# Controlador_de_velocidad_v2.net
KiCad netlist of a schematic drawn in Altium Designer
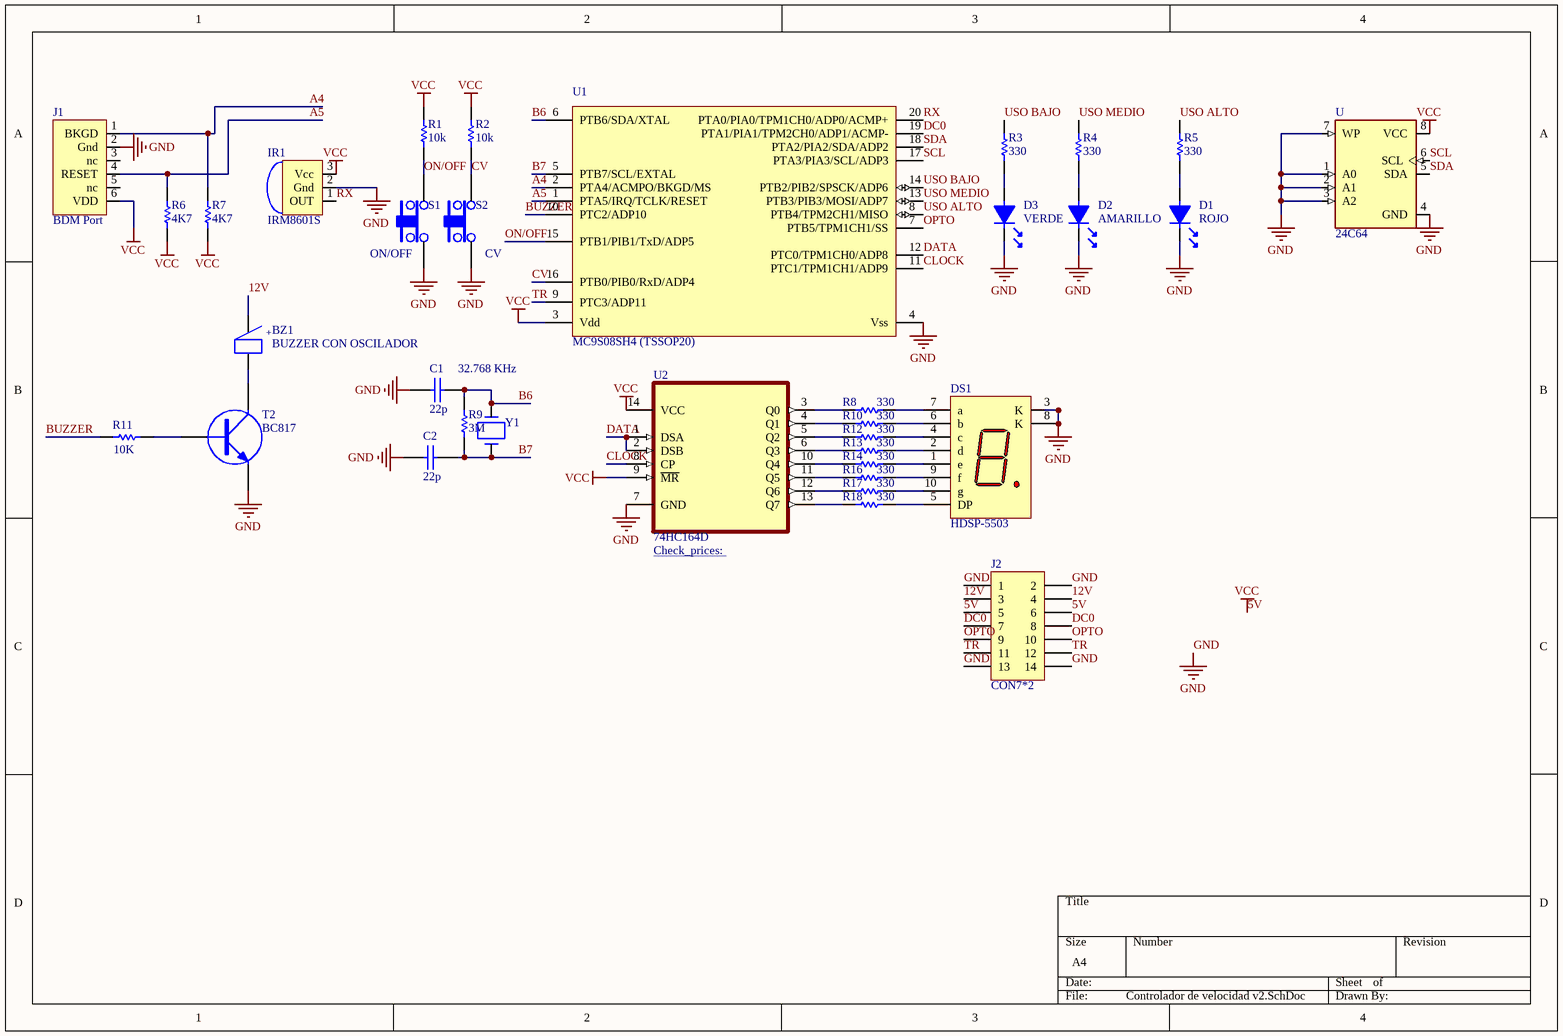
[diagram p0: Controlador de velocidad v2.SchDoc]

(export (version "E")
  (design (tool "Eeschema 10.0.6"))
  (components
    (comp (ref "BZ1")
      (value "BUZZER CON OSCILADOR")
      (footprint "BUZZER 12MM")
      (libsource (lib "LIBEBAL") (part "BUZZER"))
    )
    (comp (ref "C1") (value "22p") (footprint "0805") (libsource (lib "LIBPIOIX") (part "CAP")))
    (comp (ref "C2") (value "22p") (footprint "0805") (libsource (lib "LIBPIOIX") (part "CAP")))
    (comp (ref "D1") (value "ROJO") (footprint "LED5") (libsource (lib "LIBPIOIX") (part "LED")))
    (comp (ref "D2") (value "AMARILLO") (footprint "LED5") (libsource (lib "LIBPIOIX") (part "LED")))
    (comp (ref "D3") (value "VERDE") (footprint "LED5") (libsource (lib "LIBPIOIX") (part "LED")))
    (comp (ref "DS1")
      (value "HDSP-5503")
      (footprint "H-10")
      (description "14.22 mm Gray Surface HER 7-Segment Display: CC, RH DP")
      (fields (field (name "PUBLISHER") "Altium Limited"))
      (libsource (lib "Agilent LED Display 7-Segment, 1-Digit") (part "HDSP-5503"))
    )
    (comp (ref "IR1")
      (value "IRM8601S")
      (footprint "IRM8601S")
      (description "Sensor IR")
      (libsource (lib "*") (part "IRM8601S"))
    )
    (comp (ref "J1") (value "BDM Port") (footprint "JBDM") (libsource (lib "*") (part "JBDM")))
    (comp (ref "J2") (value "CON7*2") (footprint "SIP7*2") (libsource (lib "LIBEBAL") (part "CON7*2")))
    (comp (ref "R1") (value "10k") (footprint "0805") (libsource (lib "LIBPIOIX") (part "RES")))
    (comp (ref "R2") (value "10k") (footprint "0805") (libsource (lib "LIBPIOIX") (part "RES")))
    (comp (ref "R3") (value "330") (footprint "0805") (libsource (lib "LIBPIOIX") (part "RES")))
    (comp (ref "R4") (value "330") (footprint "0805") (libsource (lib "LIBPIOIX") (part "RES")))
    (comp (ref "R5") (value "330") (footprint "0805") (libsource (lib "LIBPIOIX") (part "RES")))
    (comp (ref "R6") (value "4K7") (footprint "0805") (libsource (lib "LIBPIOIX") (part "RES")))
    (comp (ref "R7") (value "4K7") (footprint "0805") (libsource (lib "LIBPIOIX") (part "RES")))
    (comp (ref "R8") (value "330") (footprint "0805") (libsource (lib "LIB PIO IX") (part "RES")))
    (comp (ref "R9") (value "3M") (footprint "0805") (libsource (lib "LIB PIO IX") (part "RES")))
    (comp (ref "R10") (value "330") (footprint "0805") (libsource (lib "LIB PIO IX") (part "RES")))
    (comp (ref "R11") (value "10K") (footprint "0805") (libsource (lib "LIBPIOIX") (part "RES")))
    (comp (ref "R12") (value "330") (footprint "0805") (libsource (lib "LIB PIO IX") (part "RES")))
    (comp (ref "R13") (value "330") (footprint "0805") (libsource (lib "LIB PIO IX") (part "RES")))
    (comp (ref "R14") (value "330") (footprint "0805") (libsource (lib "LIB PIO IX") (part "RES")))
    (comp (ref "R16") (value "330") (footprint "0805") (libsource (lib "LIB PIO IX") (part "RES")))
    (comp (ref "R17") (value "330") (footprint "0805") (libsource (lib "LIB PIO IX") (part "RES")))
    (comp (ref "R18") (value "330") (footprint "0805") (libsource (lib "LIB PIO IX") (part "RES")))
    (comp (ref "S1")
      (value "ON/OFF")
      (footprint "TACTSWITCH")
      (libsource (lib "LIBPIOIX") (part "TACT SWITCH"))
    )
    (comp (ref "S2") (value "CV") (footprint "TACTSWITCH") (libsource (lib "LIBPIOIX") (part "TACT SWITCH")))
    (comp (ref "T2") (value "BC817") (footprint "SOT23") (libsource (lib "LIBPIOIX") (part "TRANSISTOR NPN")))
    (comp (ref "U")
      (value "24C64")
      (footprint "SOIC127P600X175-8N")
      (description "EEPROM Memory IC 256Kb _32K x 8_ I²C 1MHz 550ns 8-SOIC")
      (fields
        (field (name "MP") "AT24C256C-SSHL-T")
        (field (name "DIGI-KEY_PART_NUMBER") "AT24C256C-SSHL-TCT-ND")
      )
      (libsource (lib "AT24C256C-SSHL-T") (part "AT24C256C-SSHL-T"))
    )
    (comp (ref "U1")
      (value "MC9S08SH4 (TSSOP20)")
      (footprint "TSSOP20")
      (libsource (lib "*") (part "MC9S08SH8_20"))
    )
    (comp (ref "U2")
      (value "74HC164D")
      (footprint "SOIC127P600X175-14N")
      (description "Shift Shift Register 1 Element 8 Bit 14-SO")
      (fields (field (name "MF") "Nexperia USA") (field (name "MP") "74HC164D,653"))
      (libsource (lib "74HC164D_653") (part "74HC164D,653"))
    )
    (comp (ref "Y1") (value "32.768 KHz") (footprint "X32768") (libsource (lib "*") (part "CRYSTAL")))
  )
  (nets
    (net (code "1") (name "/12V") (class "Default")
      (node (ref "BZ1") (pin "1") (pinfunction "1_1") (pintype "passive"))
      (node (ref "J2") (pin "3") (pinfunction "3_3") (pintype "passive"))
      (node (ref "J2") (pin "4") (pinfunction "4_4") (pintype "passive"))
    )
    (net (code "2") (name "/A4") (class "Default")
      (node (ref "J1") (pin "1") (pinfunction "BKGD_1") (pintype "passive"))
      (node (ref "R7") (pin "2") (pinfunction "2_2") (pintype "passive"))
      (node (ref "U1") (pin "2") (pinfunction "PTA4/ACMPO/BKGD/MS_2") (pintype "passive"))
    )
    (net (code "3") (name "/A5") (class "Default")
      (node (ref "J1") (pin "4") (pinfunction "RESET_4") (pintype "passive"))
      (node (ref "R6") (pin "2") (pinfunction "2_2") (pintype "passive"))
      (node (ref "U1") (pin "1") (pinfunction "PTA5/IRQ/TCLK/RESET_1") (pintype "passive"))
    )
    (net (code "4") (name "/B6") (class "Default")
      (node (ref "C1") (pin "1") (pinfunction "1_1") (pintype "passive"))
      (node (ref "R9") (pin "2") (pinfunction "2_2") (pintype "passive"))
      (node (ref "U1") (pin "6") (pinfunction "PTB6/SDA/XTAL_6") (pintype "passive"))
      (node (ref "Y1") (pin "2") (pinfunction "2_2") (pintype "passive"))
    )
    (net (code "5") (name "/B7") (class "Default")
      (node (ref "C2") (pin "1") (pinfunction "1_1") (pintype "passive"))
      (node (ref "R9") (pin "1") (pinfunction "1_1") (pintype "passive"))
      (node (ref "U1") (pin "5") (pinfunction "PTB7/SCL/EXTAL_5") (pintype "passive"))
      (node (ref "Y1") (pin "1") (pinfunction "1_1") (pintype "passive"))
    )
    (net (code "6") (name "/BUZZER") (class "Default")
      (node (ref "R11") (pin "1") (pinfunction "1_1") (pintype "passive"))
      (node (ref "U1") (pin "10") (pinfunction "PTC2/ADP10_10") (pintype "passive"))
    )
    (net (code "7") (name "/CLOCK") (class "Default")
      (node (ref "U1") (pin "11") (pinfunction "PTC1/TPM1CH1/ADP9_11") (pintype "passive"))
      (node (ref "U2") (pin "8") (pinfunction "CP_8") (pintype "input"))
    )
    (net (code "8") (name "/CV") (class "Default")
      (node (ref "R2") (pin "1") (pinfunction "1_1") (pintype "passive"))
      (node (ref "S2") (pin "2") (pinfunction "2_2") (pintype "passive"))
      (node (ref "U1") (pin "16") (pinfunction "PTB0/PIB0/RxD/ADP4_16") (pintype "passive"))
    )
    (net (code "9") (name "/DATA") (class "Default")
      (node (ref "U1") (pin "12") (pinfunction "PTC0/TPM1CH0/ADP8_12") (pintype "passive"))
      (node (ref "U2") (pin "1") (pinfunction "DSA_1") (pintype "input"))
      (node (ref "U2") (pin "2") (pinfunction "DSB_2") (pintype "input"))
    )
    (net (code "10") (name "/DC0") (class "Default")
      (node (ref "J2") (pin "7") (pinfunction "7_7") (pintype "passive"))
      (node (ref "J2") (pin "8") (pinfunction "8_8") (pintype "passive"))
      (node (ref "U1") (pin "19") (pinfunction "PTA1/PIA1/TPM2CH0/ADP1/ACMP-_19") (pintype "passive"))
    )
    (net (code "11") (name "/ON{slash}OFF") (class "Default")
      (node (ref "R1") (pin "1") (pinfunction "1_1") (pintype "passive"))
      (node (ref "S1") (pin "2") (pinfunction "2_2") (pintype "passive"))
      (node (ref "U1") (pin "15") (pinfunction "PTB1/PIB1/TxD/ADP5_15") (pintype "passive"))
    )
    (net (code "12") (name "/OPTO") (class "Default")
      (node (ref "J2") (pin "10") (pinfunction "10_10") (pintype "passive"))
      (node (ref "J2") (pin "9") (pinfunction "9_9") (pintype "passive"))
      (node (ref "U1") (pin "7") (pinfunction "PTB5/TPM1CH1/SS_7") (pintype "passive"))
    )
    (net (code "13") (name "/RX") (class "Default")
      (node (ref "IR1") (pin "1") (pinfunction "OUT_1") (pintype "passive"))
      (node (ref "U1") (pin "20") (pinfunction "PTA0/PIA0/TPM1CH0/ADP0/ACMP+_20") (pintype "passive"))
    )
    (net (code "14") (name "/SCL") (class "Default")
      (node (ref "U") (pin "6") (pinfunction "SCL_6") (pintype "input"))
      (node (ref "U1") (pin "17") (pinfunction "PTA3/PIA3/SCL/ADP3_17") (pintype "passive"))
    )
    (net (code "15") (name "/SDA") (class "Default")
      (node (ref "U") (pin "5") (pinfunction "SDA_5") (pintype "bidirectional"))
      (node (ref "U1") (pin "18") (pinfunction "PTA2/PIA2/SDA/ADP2_18") (pintype "passive"))
    )
    (net (code "16") (name "/TR") (class "Default")
      (node (ref "J2") (pin "11") (pinfunction "11_11") (pintype "passive"))
      (node (ref "J2") (pin "12") (pinfunction "12_12") (pintype "passive"))
      (node (ref "U1") (pin "9") (pinfunction "PTC3/ADP11_9") (pintype "passive"))
    )
    (net (code "17") (name "/USO ALTO") (class "Default")
      (node (ref "R5") (pin "2") (pinfunction "2_2") (pintype "passive"))
      (node (ref "U1") (pin "8") (pinfunction "PTB4/TPM2CH1/MISO_8") (pintype "bidirectional"))
    )
    (net (code "18") (name "/USO BAJO") (class "Default")
      (node (ref "R3") (pin "2") (pinfunction "2_2") (pintype "passive"))
      (node (ref "U1") (pin "14") (pinfunction "PTB2/PIB2/SPSCK/ADP6_14") (pintype "bidirectional"))
    )
    (net (code "19") (name "/USO MEDIO") (class "Default")
      (node (ref "R4") (pin "2") (pinfunction "2_2") (pintype "passive"))
      (node (ref "U1") (pin "13") (pinfunction "PTB3/PIB3/MOSI/ADP7_13") (pintype "bidirectional"))
    )
    (net (code "20") (name "GND") (class "Default")
      (node (ref "C1") (pin "2") (pinfunction "2_2") (pintype "passive"))
      (node (ref "C2") (pin "2") (pinfunction "2_2") (pintype "passive"))
      (node (ref "D1") (pin "2") (pinfunction "2_2") (pintype "passive"))
      (node (ref "D2") (pin "2") (pinfunction "2_2") (pintype "passive"))
      (node (ref "D3") (pin "2") (pinfunction "2_2") (pintype "passive"))
      (node (ref "DS1") (pin "3") (pinfunction "K_3") (pintype "passive"))
      (node (ref "DS1") (pin "8") (pinfunction "K_8") (pintype "passive"))
      (node (ref "IR1") (pin "2") (pinfunction "Gnd_2") (pintype "passive"))
      (node (ref "J1") (pin "2") (pinfunction "Gnd_2") (pintype "passive"))
      (node (ref "J2") (pin "1") (pinfunction "1_1") (pintype "passive"))
      (node (ref "J2") (pin "13") (pinfunction "13_13") (pintype "passive"))
      (node (ref "J2") (pin "14") (pinfunction "14_14") (pintype "passive"))
      (node (ref "J2") (pin "2") (pinfunction "2_2") (pintype "passive"))
      (node (ref "S1") (pin "1") (pinfunction "1_1") (pintype "passive"))
      (node (ref "S2") (pin "1") (pinfunction "1_1") (pintype "passive"))
      (node (ref "T2") (pin "3") (pinfunction "E_3") (pintype "passive"))
      (node (ref "U") (pin "1") (pinfunction "A0_1") (pintype "input"))
      (node (ref "U") (pin "2") (pinfunction "A1_2") (pintype "input"))
      (node (ref "U") (pin "3") (pinfunction "A2_3") (pintype "input"))
      (node (ref "U") (pin "4") (pinfunction "GND_4") (pintype "power_in"))
      (node (ref "U") (pin "7") (pinfunction "WP_7") (pintype "input"))
      (node (ref "U1") (pin "4") (pinfunction "Vss_4") (pintype "passive"))
      (node (ref "U2") (pin "7") (pinfunction "GND_7") (pintype "passive"))
    )
    (net (code "21") (name "Net-(D1-Pad1)") (class "Default")
      (node (ref "D1") (pin "1") (pinfunction "1_1") (pintype "passive"))
      (node (ref "R5") (pin "1") (pinfunction "1_1") (pintype "passive"))
    )
    (net (code "22") (name "Net-(D2-Pad1)") (class "Default")
      (node (ref "D2") (pin "1") (pinfunction "1_1") (pintype "passive"))
      (node (ref "R4") (pin "1") (pinfunction "1_1") (pintype "passive"))
    )
    (net (code "23") (name "Net-(D3-Pad1)") (class "Default")
      (node (ref "D3") (pin "1") (pinfunction "1_1") (pintype "passive"))
      (node (ref "R3") (pin "1") (pinfunction "1_1") (pintype "passive"))
    )
    (net (code "24") (name "Net-(DS1-DP)") (class "Default")
      (node (ref "DS1") (pin "5") (pinfunction "DP_5") (pintype "passive"))
      (node (ref "R18") (pin "2") (pinfunction "2_2") (pintype "passive"))
    )
    (net (code "25") (name "Net-(DS1-a)") (class "Default")
      (node (ref "DS1") (pin "7") (pinfunction "a_7") (pintype "passive"))
      (node (ref "R8") (pin "2") (pinfunction "2_2") (pintype "passive"))
    )
    (net (code "26") (name "Net-(DS1-b)") (class "Default")
      (node (ref "DS1") (pin "6") (pinfunction "b_6") (pintype "passive"))
      (node (ref "R10") (pin "2") (pinfunction "2_2") (pintype "passive"))
    )
    (net (code "27") (name "Net-(DS1-c)") (class "Default")
      (node (ref "DS1") (pin "4") (pinfunction "c_4") (pintype "passive"))
      (node (ref "R12") (pin "2") (pinfunction "2_2") (pintype "passive"))
    )
    (net (code "28") (name "Net-(DS1-d)") (class "Default")
      (node (ref "DS1") (pin "2") (pinfunction "d_2") (pintype "passive"))
      (node (ref "R13") (pin "2") (pinfunction "2_2") (pintype "passive"))
    )
    (net (code "29") (name "Net-(DS1-e)") (class "Default")
      (node (ref "DS1") (pin "1") (pinfunction "e_1") (pintype "passive"))
      (node (ref "R14") (pin "2") (pinfunction "2_2") (pintype "passive"))
    )
    (net (code "30") (name "Net-(DS1-f)") (class "Default")
      (node (ref "DS1") (pin "9") (pinfunction "f_9") (pintype "passive"))
      (node (ref "R16") (pin "2") (pinfunction "2_2") (pintype "passive"))
    )
    (net (code "31") (name "Net-(DS1-g)") (class "Default")
      (node (ref "DS1") (pin "10") (pinfunction "g_10") (pintype "passive"))
      (node (ref "R17") (pin "2") (pinfunction "2_2") (pintype "passive"))
    )
    (net (code "32") (name "Net-(T2-B)") (class "Default")
      (node (ref "R11") (pin "2") (pinfunction "2_2") (pintype "passive"))
      (node (ref "T2") (pin "1") (pinfunction "B_1") (pintype "passive"))
    )
    (net (code "33") (name "Net-(T2-C)") (class "Default")
      (node (ref "BZ1") (pin "2") (pinfunction "2_2") (pintype "passive"))
      (node (ref "T2") (pin "2") (pinfunction "C_2") (pintype "passive"))
    )
    (net (code "34") (name "Net-(U2-Q0)") (class "Default")
      (node (ref "R8") (pin "1") (pinfunction "1_1") (pintype "passive"))
      (node (ref "U2") (pin "3") (pinfunction "Q0_3") (pintype "output"))
    )
    (net (code "35") (name "Net-(U2-Q1)") (class "Default")
      (node (ref "R10") (pin "1") (pinfunction "1_1") (pintype "passive"))
      (node (ref "U2") (pin "4") (pinfunction "Q1_4") (pintype "output"))
    )
    (net (code "36") (name "Net-(U2-Q2)") (class "Default")
      (node (ref "R12") (pin "1") (pinfunction "1_1") (pintype "passive"))
      (node (ref "U2") (pin "5") (pinfunction "Q2_5") (pintype "output"))
    )
    (net (code "37") (name "Net-(U2-Q3)") (class "Default")
      (node (ref "R13") (pin "1") (pinfunction "1_1") (pintype "passive"))
      (node (ref "U2") (pin "6") (pinfunction "Q3_6") (pintype "output"))
    )
    (net (code "38") (name "Net-(U2-Q4)") (class "Default")
      (node (ref "R14") (pin "1") (pinfunction "1_1") (pintype "passive"))
      (node (ref "U2") (pin "10") (pinfunction "Q4_10") (pintype "output"))
    )
    (net (code "39") (name "Net-(U2-Q5)") (class "Default")
      (node (ref "R16") (pin "1") (pinfunction "1_1") (pintype "passive"))
      (node (ref "U2") (pin "11") (pinfunction "Q5_11") (pintype "output"))
    )
    (net (code "40") (name "Net-(U2-Q6)") (class "Default")
      (node (ref "R17") (pin "1") (pinfunction "1_1") (pintype "passive"))
      (node (ref "U2") (pin "12") (pinfunction "Q6_12") (pintype "output"))
    )
    (net (code "41") (name "Net-(U2-Q7)") (class "Default")
      (node (ref "R18") (pin "1") (pinfunction "1_1") (pintype "passive"))
      (node (ref "U2") (pin "13") (pinfunction "Q7_13") (pintype "output"))
    )
    (net (code "42") (name "VCC") (class "Default")
      (node (ref "IR1") (pin "3") (pinfunction "Vcc_3") (pintype "passive"))
      (node (ref "J1") (pin "6") (pinfunction "VDD_6") (pintype "passive"))
      (node (ref "J2") (pin "5") (pinfunction "5_5") (pintype "passive"))
      (node (ref "J2") (pin "6") (pinfunction "6_6") (pintype "passive"))
      (node (ref "R1") (pin "2") (pinfunction "2_2") (pintype "passive"))
      (node (ref "R2") (pin "2") (pinfunction "2_2") (pintype "passive"))
      (node (ref "R6") (pin "1") (pinfunction "1_1") (pintype "passive"))
      (node (ref "R7") (pin "1") (pinfunction "1_1") (pintype "passive"))
      (node (ref "U") (pin "8") (pinfunction "VCC_8") (pintype "power_in"))
      (node (ref "U1") (pin "3") (pinfunction "Vdd_3") (pintype "passive"))
      (node (ref "U2") (pin "14") (pinfunction "VCC_14") (pintype "power_in"))
      (node (ref "U2") (pin "9") (pinfunction "~{MR}_9") (pintype "input"))
    )
    (net (code "43") (name "unconnected-(J1-nc-Pad3)") (class "Default")
      (node (ref "J1") (pin "3") (pinfunction "nc_3") (pintype "passive"))
    )
    (net (code "44") (name "unconnected-(J1-nc-Pad5)") (class "Default")
      (node (ref "J1") (pin "5") (pinfunction "nc_5") (pintype "passive"))
    )
  )
)
